# mic4606_power_v2.net
KiCad netlist of a schematic drawn in EAGLE
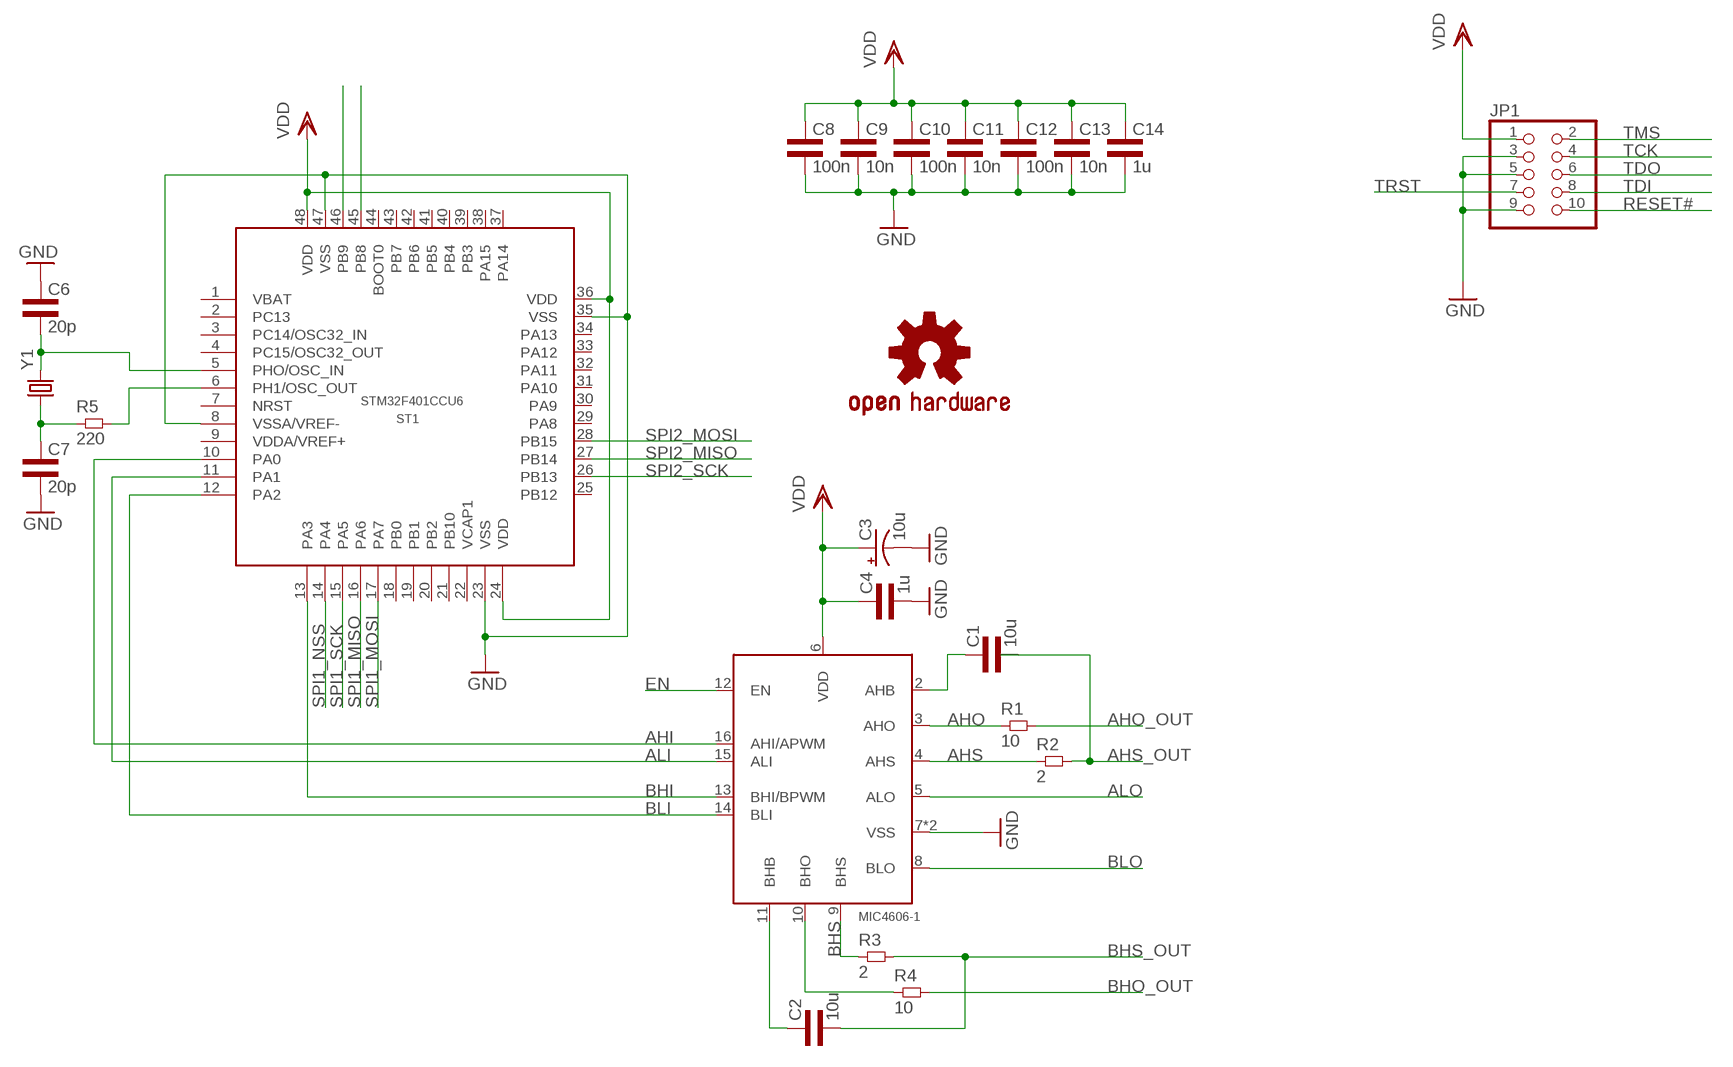
[diagram p0: schematic, sheet 1]
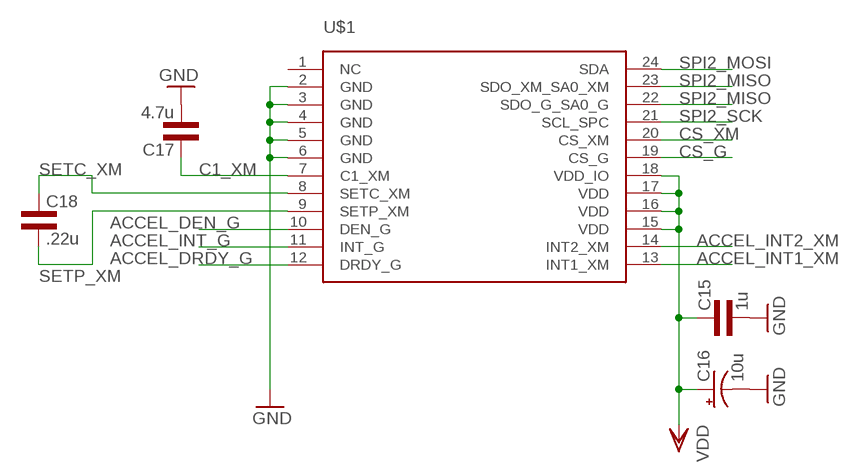
[diagram p1: schematic, sheet 2]
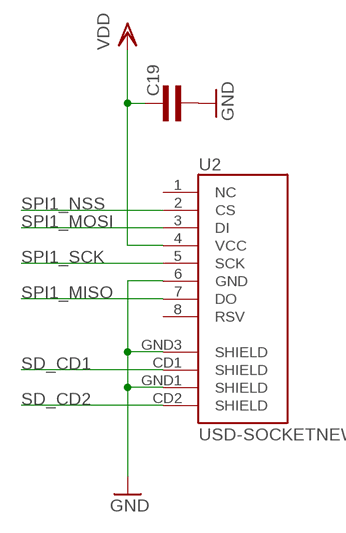
[diagram p2: schematic, sheet 3]
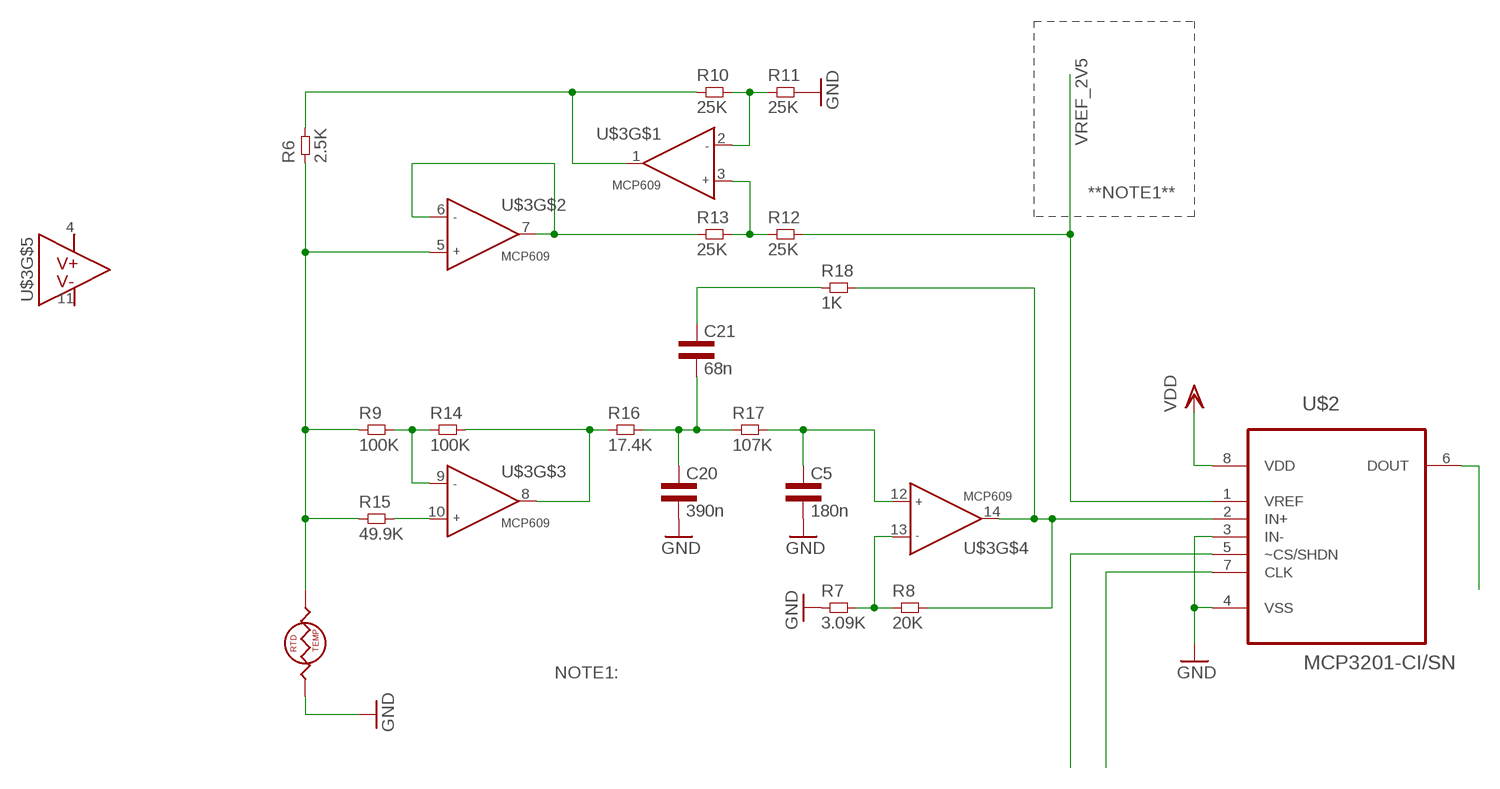
[diagram p3: schematic, sheet 4]

(export (version "E")
  (design (tool "Eeschema 10.0.6"))
  (components
    (comp (ref "C1")
      (value "10u")
      (footprint "eagle-import:0805L3")
      (libsource (lib "eagle-import") (part "CAP0805L3"))
    )
    (comp (ref "C2")
      (value "10u")
      (footprint "eagle-import:0805L3")
      (libsource (lib "eagle-import") (part "CAP0805L3"))
    )
    (comp (ref "C3")
      (value "10u")
      (footprint "eagle-import:E1,8-4")
      (libsource (lib "eagle-import") (part "CPOL-USE1.8-4"))
    )
    (comp (ref "C4")
      (value "1u")
      (footprint "eagle-import:0603L3")
      (libsource (lib "eagle-import") (part "CAP0603L3"))
    )
    (comp (ref "C6")
      (value "20p")
      (footprint "eagle-import:0603L3")
      (libsource (lib "eagle-import") (part "CAP0603L3"))
    )
    (comp (ref "C7")
      (value "20p")
      (footprint "eagle-import:0603L3")
      (libsource (lib "eagle-import") (part "CAP0603L3"))
    )
    (comp (ref "C8")
      (value "100n")
      (footprint "eagle-import:0603L3")
      (libsource (lib "eagle-import") (part "CAP0603L3"))
    )
    (comp (ref "C9")
      (value "10n")
      (footprint "eagle-import:0603L3")
      (libsource (lib "eagle-import") (part "CAP0603L3"))
    )
    (comp (ref "C10")
      (value "100n")
      (footprint "eagle-import:0603L3")
      (libsource (lib "eagle-import") (part "CAP0603L3"))
    )
    (comp (ref "C11")
      (value "10n")
      (footprint "eagle-import:0603L3")
      (libsource (lib "eagle-import") (part "CAP0603L3"))
    )
    (comp (ref "C12")
      (value "100n")
      (footprint "eagle-import:0603L3")
      (libsource (lib "eagle-import") (part "CAP0603L3"))
    )
    (comp (ref "C13")
      (value "10n")
      (footprint "eagle-import:0603L3")
      (libsource (lib "eagle-import") (part "CAP0603L3"))
    )
    (comp (ref "C14")
      (value "1u")
      (footprint "eagle-import:0805L3")
      (libsource (lib "eagle-import") (part "CAP0805L3"))
    )
    (comp (ref "JP1")
      (value "PINHD-2X5")
      (footprint "eagle-import:2X05")
      (libsource (lib "eagle-import") (part "PINHD-2X5"))
    )
    (comp (ref "LOGO1")
      (value "OSHW-LOGOM")
      (footprint "eagle-import:OSHW-LOGO-M")
      (libsource (lib "eagle-import") (part "OSHW-LOGOM"))
    )
    (comp (ref "MD1")
      (value "MIC4606-1")
      (footprint "eagle-import:QFN44-16LD-PL-2")
      (libsource (lib "eagle-import") (part "MIC4606-1"))
    )
    (comp (ref "R1")
      (value "10")
      (footprint "eagle-import:0805L3")
      (libsource (lib "eagle-import") (part "RES0805L3"))
    )
    (comp (ref "R2")
      (value "2")
      (footprint "eagle-import:0805L3")
      (libsource (lib "eagle-import") (part "RES0805L3"))
    )
    (comp (ref "R3")
      (value "2")
      (footprint "eagle-import:0805L3")
      (libsource (lib "eagle-import") (part "RES0805L3"))
    )
    (comp (ref "R4")
      (value "10")
      (footprint "eagle-import:0805L3")
      (libsource (lib "eagle-import") (part "RES0805L3"))
    )
    (comp (ref "R5")
      (value "220")
      (footprint "eagle-import:0603L3")
      (libsource (lib "eagle-import") (part "RES0603L3"))
    )
    (comp (ref "ST1")
      (value "STM32F401CCU6")
      (footprint "eagle-import:UFQFPN48")
      (libsource (lib "eagle-import") (part "STM32F401CCU6"))
    )
    (comp (ref "Y1")
      (value "CRYSTALHC49US")
      (footprint "eagle-import:HC49US")
      (libsource (lib "eagle-import") (part "CRYSTALHC49US"))
    )
    (comp (ref "C19")
      (value "CAP0603L3")
      (footprint "eagle-import:0603L3")
      (libsource (lib "eagle-import") (part "CAP0603L3"))
    )
    (comp (ref "U2")
      (value "USD-SOCKETNEW")
      (footprint "eagle-import:MICRO-SD-SOCKET-PP")
      (libsource (lib "eagle-import") (part "USD-SOCKETNEW"))
    )
    (comp (ref "C15")
      (value "1u")
      (footprint "eagle-import:0805L3")
      (libsource (lib "eagle-import") (part "CAP0805L3"))
    )
    (comp (ref "C16")
      (value "10u")
      (footprint "eagle-import:CT3216")
      (libsource (lib "eagle-import") (part "CPOL-USCT3216"))
    )
    (comp (ref "C17")
      (value "4.7u")
      (footprint "eagle-import:0603L3")
      (libsource (lib "eagle-import") (part "CAP0603L3"))
    )
    (comp (ref "C18")
      (value ".22u")
      (footprint "eagle-import:0603L3")
      (libsource (lib "eagle-import") (part "CAP0603L3"))
    )
    (comp (ref "U$1")
      (value "ST_LSM9DS0_TEMP_SENSE_LSM9DS0")
      (footprint "eagle-import:ST_LSM9DS0_TEMP_SENSE_LGA-24")
      (libsource (lib "eagle-import") (part "ST_LSM9DS0_TEMP_SENSE_LSM9DS0"))
    )
    (comp (ref "C5")
      (value "180n")
      (footprint "eagle-import:0603L3")
      (libsource (lib "eagle-import") (part "CAP0603L3"))
    )
    (comp (ref "C20")
      (value "390n")
      (footprint "eagle-import:0603L3")
      (libsource (lib "eagle-import") (part "CAP0603L3"))
    )
    (comp (ref "C21")
      (value "68n")
      (footprint "eagle-import:0603L3")
      (libsource (lib "eagle-import") (part "CAP0603L3"))
    )
    (comp (ref "R6")
      (value "2.5K")
      (footprint "eagle-import:0603L3")
      (libsource (lib "eagle-import") (part "RES0603L3"))
    )
    (comp (ref "R7")
      (value "3.09K")
      (footprint "eagle-import:0603L3")
      (libsource (lib "eagle-import") (part "RES0603L3"))
    )
    (comp (ref "R8")
      (value "20K")
      (footprint "eagle-import:0603L3")
      (libsource (lib "eagle-import") (part "RES0603L3"))
    )
    (comp (ref "R9")
      (value "100K")
      (footprint "eagle-import:0603L3")
      (libsource (lib "eagle-import") (part "RES0603L3"))
    )
    (comp (ref "R10")
      (value "25K")
      (footprint "eagle-import:0603L3")
      (libsource (lib "eagle-import") (part "RES0603L3"))
    )
    (comp (ref "R11")
      (value "25K")
      (footprint "eagle-import:0603L3")
      (libsource (lib "eagle-import") (part "RES0603L3"))
    )
    (comp (ref "R12")
      (value "25K")
      (footprint "eagle-import:0603L3")
      (libsource (lib "eagle-import") (part "RES0603L3"))
    )
    (comp (ref "R13")
      (value "25K")
      (footprint "eagle-import:0603L3")
      (libsource (lib "eagle-import") (part "RES0603L3"))
    )
    (comp (ref "R14")
      (value "100K")
      (footprint "eagle-import:0603L3")
      (libsource (lib "eagle-import") (part "RES0603L3"))
    )
    (comp (ref "R15")
      (value "49.9K")
      (footprint "eagle-import:0603L3")
      (libsource (lib "eagle-import") (part "RES0603L3"))
    )
    (comp (ref "R16")
      (value "17.4K")
      (footprint "eagle-import:0603L3")
      (libsource (lib "eagle-import") (part "RES0603L3"))
    )
    (comp (ref "R17")
      (value "107K")
      (footprint "eagle-import:0603L3")
      (libsource (lib "eagle-import") (part "RES0603L3"))
    )
    (comp (ref "R18")
      (value "1K")
      (footprint "eagle-import:0603L3")
      (libsource (lib "eagle-import") (part "RES0603L3"))
    )
    (comp (ref "RTD1")
      (value "RTD0805L1")
      (footprint "eagle-import:0805L1")
      (libsource (lib "eagle-import") (part "RTD0805L1"))
    )
    (comp (ref "U$2")
      (value "MCP3201-CI/SN")
      (footprint "eagle-import:SOIC127P600X175-8N")
      (libsource (lib "eagle-import") (part "MCP3201-CI/SN"))
    )
    (comp (ref "U$3")
      (value "MCP609")
      (footprint "eagle-import:TSSOP-14")
      (libsource (lib "eagle-import") (part "MCP609"))
    )
  )
  (nets
    (net (code "1") (name "ACCEL_DEN_G") (class "Default")
      (node (ref "U$1") (pin "10") (pinfunction "DEN_G_10") (pintype "bidirectional"))
    )
    (net (code "2") (name "ACCEL_DRDY_G") (class "Default")
      (node (ref "U$1") (pin "12") (pinfunction "DRDY_G_12") (pintype "bidirectional"))
    )
    (net (code "3") (name "ACCEL_INT1_XM") (class "Default")
      (node (ref "U$1") (pin "13") (pinfunction "INT1_XM_13") (pintype "bidirectional"))
    )
    (net (code "4") (name "ACCEL_INT2_XM") (class "Default")
      (node (ref "U$1") (pin "14") (pinfunction "INT2_XM_14") (pintype "bidirectional"))
    )
    (net (code "5") (name "ACCEL_INT_G") (class "Default")
      (node (ref "U$1") (pin "11") (pinfunction "INT_G_11") (pintype "bidirectional"))
    )
    (net (code "6") (name "AHI") (class "Default")
      (node (ref "MD1") (pin "16") (pinfunction "AHI/APWM_16") (pintype "bidirectional"))
      (node (ref "ST1") (pin "10") (pinfunction "PA0_10") (pintype "bidirectional"))
    )
    (net (code "7") (name "AHO") (class "Default")
      (node (ref "MD1") (pin "3") (pinfunction "AHO_3") (pintype "bidirectional"))
      (node (ref "R1") (pin "1") (pinfunction "1_1") (pintype "bidirectional"))
    )
    (net (code "8") (name "AHO_OUT") (class "Default")
      (node (ref "R1") (pin "2") (pinfunction "2_2") (pintype "bidirectional"))
    )
    (net (code "9") (name "AHS") (class "Default")
      (node (ref "MD1") (pin "4") (pinfunction "AHS_4") (pintype "bidirectional"))
      (node (ref "R2") (pin "1") (pinfunction "1_1") (pintype "bidirectional"))
    )
    (net (code "10") (name "AHS_OUT") (class "Default")
      (node (ref "C1") (pin "2") (pinfunction "2_2") (pintype "bidirectional"))
      (node (ref "R2") (pin "2") (pinfunction "2_2") (pintype "bidirectional"))
    )
    (net (code "11") (name "ALI") (class "Default")
      (node (ref "MD1") (pin "15") (pinfunction "ALI_15") (pintype "bidirectional"))
      (node (ref "ST1") (pin "11") (pinfunction "PA1_11") (pintype "bidirectional"))
    )
    (net (code "12") (name "ALO") (class "Default")
      (node (ref "MD1") (pin "5") (pinfunction "ALO_5") (pintype "bidirectional"))
    )
    (net (code "13") (name "BHI") (class "Default")
      (node (ref "MD1") (pin "13") (pinfunction "BHI/BPWM_13") (pintype "bidirectional"))
      (node (ref "ST1") (pin "13") (pinfunction "PA3_13") (pintype "bidirectional"))
    )
    (net (code "14") (name "BHO_OUT") (class "Default")
      (node (ref "R4") (pin "2") (pinfunction "2_2") (pintype "bidirectional"))
    )
    (net (code "15") (name "BHS") (class "Default")
      (node (ref "MD1") (pin "9") (pinfunction "BHS_9") (pintype "bidirectional"))
      (node (ref "R3") (pin "1") (pinfunction "1_1") (pintype "bidirectional"))
    )
    (net (code "16") (name "BHS_OUT") (class "Default")
      (node (ref "C2") (pin "2") (pinfunction "2_2") (pintype "bidirectional"))
      (node (ref "R3") (pin "2") (pinfunction "2_2") (pintype "bidirectional"))
    )
    (net (code "17") (name "BLI") (class "Default")
      (node (ref "MD1") (pin "14") (pinfunction "BLI_14") (pintype "bidirectional"))
      (node (ref "ST1") (pin "12") (pinfunction "PA2_12") (pintype "bidirectional"))
    )
    (net (code "18") (name "BLO") (class "Default")
      (node (ref "MD1") (pin "8") (pinfunction "BLO_8") (pintype "bidirectional"))
    )
    (net (code "19") (name "C1_XM") (class "Default")
      (node (ref "C17") (pin "P$1") (pinfunction "1_P$1") (pintype "bidirectional"))
      (node (ref "U$1") (pin "7") (pinfunction "C1_XM_7") (pintype "bidirectional"))
    )
    (net (code "20") (name "CS_G") (class "Default")
      (node (ref "ST1") (pin "45") (pinfunction "PB8_45") (pintype "bidirectional"))
      (node (ref "U$1") (pin "19") (pinfunction "CS_G_19") (pintype "bidirectional"))
    )
    (net (code "21") (name "CS_XM") (class "Default")
      (node (ref "ST1") (pin "46") (pinfunction "PB9_46") (pintype "bidirectional"))
      (node (ref "U$1") (pin "20") (pinfunction "CS_XM_20") (pintype "bidirectional"))
    )
    (net (code "22") (name "EN") (class "Default")
      (node (ref "MD1") (pin "12") (pinfunction "EN_12") (pintype "bidirectional"))
    )
    (net (code "23") (name "GND") (class "Default")
      (node (ref "C10") (pin "P$2") (pinfunction "2_P$2") (pintype "bidirectional"))
      (node (ref "C11") (pin "P$2") (pinfunction "2_P$2") (pintype "bidirectional"))
      (node (ref "C12") (pin "P$2") (pinfunction "2_P$2") (pintype "bidirectional"))
      (node (ref "C13") (pin "P$2") (pinfunction "2_P$2") (pintype "bidirectional"))
      (node (ref "C14") (pin "2") (pinfunction "2_2") (pintype "bidirectional"))
      (node (ref "C15") (pin "2") (pinfunction "2_2") (pintype "bidirectional"))
      (node (ref "C16") (pin "-") (pinfunction "-_-") (pintype "passive"))
      (node (ref "C17") (pin "P$2") (pinfunction "2_P$2") (pintype "bidirectional"))
      (node (ref "C19") (pin "P$2") (pinfunction "2_P$2") (pintype "bidirectional"))
      (node (ref "C20") (pin "P$2") (pinfunction "2_P$2") (pintype "bidirectional"))
      (node (ref "C3") (pin "-") (pinfunction "-_-") (pintype "passive"))
      (node (ref "C4") (pin "P$2") (pinfunction "2_P$2") (pintype "bidirectional"))
      (node (ref "C5") (pin "P$2") (pinfunction "2_P$2") (pintype "bidirectional"))
      (node (ref "C6") (pin "P$1") (pinfunction "1_P$1") (pintype "bidirectional"))
      (node (ref "C7") (pin "P$2") (pinfunction "2_P$2") (pintype "bidirectional"))
      (node (ref "C8") (pin "P$2") (pinfunction "2_P$2") (pintype "bidirectional"))
      (node (ref "C9") (pin "P$2") (pinfunction "2_P$2") (pintype "bidirectional"))
      (node (ref "JP1") (pin "3") (pinfunction "3_3") (pintype "passive"))
      (node (ref "JP1") (pin "5") (pinfunction "5_5") (pintype "passive"))
      (node (ref "JP1") (pin "9") (pinfunction "9_9") (pintype "passive"))
      (node (ref "MD1") (pin "7") (pinfunction "VSS_7") (pintype "bidirectional"))
      (node (ref "MD1") (pin "TP") (pinfunction "VSS_TP") (pintype "bidirectional"))
      (node (ref "R11") (pin "P$2") (pinfunction "2_P$2") (pintype "bidirectional"))
      (node (ref "R7") (pin "P$1") (pinfunction "1_P$1") (pintype "bidirectional"))
      (node (ref "RTD1") (pin "1") (pinfunction "1_1") (pintype "bidirectional"))
      (node (ref "ST1") (pin "23") (pinfunction "VSS_23") (pintype "bidirectional"))
      (node (ref "ST1") (pin "35") (pinfunction "VSS_35") (pintype "bidirectional"))
      (node (ref "ST1") (pin "47") (pinfunction "VSS_47") (pintype "bidirectional"))
      (node (ref "ST1") (pin "8") (pinfunction "VSSA/VREF-_8") (pintype "bidirectional"))
      (node (ref "U$1") (pin "2") (pinfunction "GND_2") (pintype "bidirectional"))
      (node (ref "U$1") (pin "3") (pinfunction "GND_3") (pintype "bidirectional"))
      (node (ref "U$1") (pin "4") (pinfunction "GND_4") (pintype "bidirectional"))
      (node (ref "U$1") (pin "5") (pinfunction "GND_5") (pintype "bidirectional"))
      (node (ref "U$1") (pin "6") (pinfunction "GND_6") (pintype "bidirectional"))
      (node (ref "U$2") (pin "3") (pinfunction "IN-_3") (pintype "input"))
      (node (ref "U$2") (pin "4") (pinfunction "VSS_4") (pintype "power_in"))
      (node (ref "U2") (pin "6") (pinfunction "GND_6") (pintype "bidirectional"))
      (node (ref "U2") (pin "GND1") (pinfunction "SHIELD_GND1") (pintype "bidirectional"))
      (node (ref "U2") (pin "GND3") (pinfunction "SHIELD_GND3") (pintype "bidirectional"))
    )
    (net (code "24") (name "Net-(C5-1)") (class "Default")
      (node (ref "C5") (pin "P$1") (pinfunction "1_P$1") (pintype "bidirectional"))
      (node (ref "R17") (pin "P$2") (pinfunction "2_P$2") (pintype "bidirectional"))
      (node (ref "U$3") (pin "12") (pinfunction "INA+_12") (pintype "bidirectional"))
    )
    (net (code "25") (name "Net-(C6-2)") (class "Default")
      (node (ref "C6") (pin "P$2") (pinfunction "2_P$2") (pintype "bidirectional"))
      (node (ref "ST1") (pin "5") (pinfunction "PHO/OSC_IN_5") (pintype "bidirectional"))
      (node (ref "Y1") (pin "2") (pinfunction "2_2") (pintype "passive"))
    )
    (net (code "26") (name "Net-(C7-1)") (class "Default")
      (node (ref "C7") (pin "P$1") (pinfunction "1_P$1") (pintype "bidirectional"))
      (node (ref "R5") (pin "P$1") (pinfunction "1_P$1") (pintype "bidirectional"))
      (node (ref "Y1") (pin "1") (pinfunction "1_1") (pintype "passive"))
    )
    (net (code "27") (name "Net-(C20-1)") (class "Default")
      (node (ref "C20") (pin "P$1") (pinfunction "1_P$1") (pintype "bidirectional"))
      (node (ref "C21") (pin "P$2") (pinfunction "2_P$2") (pintype "bidirectional"))
      (node (ref "R16") (pin "P$2") (pinfunction "2_P$2") (pintype "bidirectional"))
      (node (ref "R17") (pin "P$1") (pinfunction "1_P$1") (pintype "bidirectional"))
    )
    (net (code "28") (name "Net-(C21-1)") (class "Default")
      (node (ref "C21") (pin "P$1") (pinfunction "1_P$1") (pintype "bidirectional"))
      (node (ref "R18") (pin "P$1") (pinfunction "1_P$1") (pintype "bidirectional"))
    )
    (net (code "29") (name "Net-(MD1-AHB)") (class "Default")
      (node (ref "C1") (pin "1") (pinfunction "1_1") (pintype "bidirectional"))
      (node (ref "MD1") (pin "2") (pinfunction "AHB_2") (pintype "bidirectional"))
    )
    (net (code "30") (name "Net-(MD1-BHB)") (class "Default")
      (node (ref "C2") (pin "1") (pinfunction "1_1") (pintype "bidirectional"))
      (node (ref "MD1") (pin "11") (pinfunction "BHB_11") (pintype "bidirectional"))
    )
    (net (code "31") (name "Net-(MD1-BHO)") (class "Default")
      (node (ref "MD1") (pin "10") (pinfunction "BHO_10") (pintype "bidirectional"))
      (node (ref "R4") (pin "1") (pinfunction "1_1") (pintype "bidirectional"))
    )
    (net (code "32") (name "Net-(R5-2)") (class "Default")
      (node (ref "R5") (pin "P$2") (pinfunction "2_P$2") (pintype "bidirectional"))
      (node (ref "ST1") (pin "6") (pinfunction "PH1/OSC_OUT_6") (pintype "bidirectional"))
    )
    (net (code "33") (name "Net-(R7-2)") (class "Default")
      (node (ref "R7") (pin "P$2") (pinfunction "2_P$2") (pintype "bidirectional"))
      (node (ref "R8") (pin "P$1") (pinfunction "1_P$1") (pintype "bidirectional"))
      (node (ref "U$3") (pin "13") (pinfunction "INA-_13") (pintype "bidirectional"))
    )
    (net (code "34") (name "Net-(R10-1)") (class "Default")
      (node (ref "R10") (pin "P$1") (pinfunction "1_P$1") (pintype "bidirectional"))
      (node (ref "R6") (pin "P$2") (pinfunction "2_P$2") (pintype "bidirectional"))
      (node (ref "U$3") (pin "1") (pinfunction "OUTA_1") (pintype "bidirectional"))
    )
    (net (code "35") (name "Net-(R10-2)") (class "Default")
      (node (ref "R10") (pin "P$2") (pinfunction "2_P$2") (pintype "bidirectional"))
      (node (ref "R11") (pin "P$1") (pinfunction "1_P$1") (pintype "bidirectional"))
      (node (ref "U$3") (pin "2") (pinfunction "INA-_2") (pintype "bidirectional"))
    )
    (net (code "36") (name "Net-(R12-1)") (class "Default")
      (node (ref "R12") (pin "P$1") (pinfunction "1_P$1") (pintype "bidirectional"))
      (node (ref "R13") (pin "P$2") (pinfunction "2_P$2") (pintype "bidirectional"))
      (node (ref "U$3") (pin "3") (pinfunction "INA+_3") (pintype "bidirectional"))
    )
    (net (code "37") (name "Net-(R13-1)") (class "Default")
      (node (ref "R13") (pin "P$1") (pinfunction "1_P$1") (pintype "bidirectional"))
      (node (ref "U$3") (pin "6") (pinfunction "INA-_6") (pintype "bidirectional"))
      (node (ref "U$3") (pin "7") (pinfunction "OUTA_7") (pintype "bidirectional"))
    )
    (net (code "38") (name "Net-(R14-1)") (class "Default")
      (node (ref "R14") (pin "P$1") (pinfunction "1_P$1") (pintype "bidirectional"))
      (node (ref "R9") (pin "P$2") (pinfunction "2_P$2") (pintype "bidirectional"))
      (node (ref "U$3") (pin "9") (pinfunction "INA-_9") (pintype "bidirectional"))
    )
    (net (code "39") (name "Net-(R14-2)") (class "Default")
      (node (ref "R14") (pin "P$2") (pinfunction "2_P$2") (pintype "bidirectional"))
      (node (ref "R16") (pin "P$1") (pinfunction "1_P$1") (pintype "bidirectional"))
      (node (ref "U$3") (pin "8") (pinfunction "OUTA_8") (pintype "bidirectional"))
    )
    (net (code "40") (name "Net-(R15-1)") (class "Default")
      (node (ref "R15") (pin "P$1") (pinfunction "1_P$1") (pintype "bidirectional"))
      (node (ref "R6") (pin "P$1") (pinfunction "1_P$1") (pintype "bidirectional"))
      (node (ref "R9") (pin "P$1") (pinfunction "1_P$1") (pintype "bidirectional"))
      (node (ref "RTD1") (pin "2") (pinfunction "2_2") (pintype "bidirectional"))
      (node (ref "U$3") (pin "5") (pinfunction "INA+_5") (pintype "bidirectional"))
    )
    (net (code "41") (name "Net-(R15-2)") (class "Default")
      (node (ref "R15") (pin "P$2") (pinfunction "2_P$2") (pintype "bidirectional"))
      (node (ref "U$3") (pin "10") (pinfunction "INA+_10") (pintype "bidirectional"))
    )
    (net (code "42") (name "Net-(R18-2)") (class "Default")
      (node (ref "R18") (pin "P$2") (pinfunction "2_P$2") (pintype "bidirectional"))
      (node (ref "R8") (pin "P$2") (pinfunction "2_P$2") (pintype "bidirectional"))
      (node (ref "U$2") (pin "2") (pinfunction "IN+_2") (pintype "input"))
      (node (ref "U$3") (pin "14") (pinfunction "OUTA_14") (pintype "bidirectional"))
    )
    (net (code "43") (name "RESET#") (class "Default")
      (node (ref "JP1") (pin "10") (pinfunction "10_10") (pintype "passive"))
    )
    (net (code "44") (name "SD_CD1") (class "Default")
      (node (ref "U2") (pin "CD1") (pinfunction "SHIELD_CD1") (pintype "bidirectional"))
    )
    (net (code "45") (name "SD_CD2") (class "Default")
      (node (ref "U2") (pin "CD2") (pinfunction "SHIELD_CD2") (pintype "bidirectional"))
    )
    (net (code "46") (name "SETC_XM") (class "Default")
      (node (ref "C18") (pin "P$1") (pinfunction "1_P$1") (pintype "bidirectional"))
      (node (ref "U$1") (pin "8") (pinfunction "SETC_XM_8") (pintype "bidirectional"))
    )
    (net (code "47") (name "SETP_XM") (class "Default")
      (node (ref "C18") (pin "P$2") (pinfunction "2_P$2") (pintype "bidirectional"))
      (node (ref "U$1") (pin "9") (pinfunction "SETP_XM_9") (pintype "bidirectional"))
    )
    (net (code "48") (name "SPI1_MISO") (class "Default")
      (node (ref "ST1") (pin "16") (pinfunction "PA6_16") (pintype "bidirectional"))
      (node (ref "U2") (pin "7") (pinfunction "DO_7") (pintype "bidirectional"))
    )
    (net (code "49") (name "SPI1_MOSI") (class "Default")
      (node (ref "ST1") (pin "17") (pinfunction "PA7_17") (pintype "bidirectional"))
      (node (ref "U2") (pin "3") (pinfunction "DI_3") (pintype "bidirectional"))
    )
    (net (code "50") (name "SPI1_NSS") (class "Default")
      (node (ref "ST1") (pin "14") (pinfunction "PA4_14") (pintype "bidirectional"))
      (node (ref "U2") (pin "2") (pinfunction "CS_2") (pintype "bidirectional"))
    )
    (net (code "51") (name "SPI1_SCK") (class "Default")
      (node (ref "ST1") (pin "15") (pinfunction "PA5_15") (pintype "bidirectional"))
      (node (ref "U2") (pin "5") (pinfunction "SCK_5") (pintype "bidirectional"))
    )
    (net (code "52") (name "SPI2_MISO") (class "Default")
      (node (ref "ST1") (pin "27") (pinfunction "PB14_27") (pintype "bidirectional"))
      (node (ref "U$1") (pin "22") (pinfunction "SDO_G_SA0_G_22") (pintype "bidirectional"))
      (node (ref "U$1") (pin "23") (pinfunction "SDO_XM_SA0_XM_23") (pintype "bidirectional"))
    )
    (net (code "53") (name "SPI2_MOSI") (class "Default")
      (node (ref "ST1") (pin "28") (pinfunction "PB15_28") (pintype "bidirectional"))
      (node (ref "U$1") (pin "24") (pinfunction "SDA_24") (pintype "bidirectional"))
    )
    (net (code "54") (name "SPI2_SCK") (class "Default")
      (node (ref "ST1") (pin "26") (pinfunction "PB13_26") (pintype "bidirectional"))
      (node (ref "U$1") (pin "21") (pinfunction "SCL_SPC_21") (pintype "bidirectional"))
    )
    (net (code "55") (name "TCK") (class "Default")
      (node (ref "JP1") (pin "4") (pinfunction "4_4") (pintype "passive"))
    )
    (net (code "56") (name "TDI") (class "Default")
      (node (ref "JP1") (pin "8") (pinfunction "8_8") (pintype "passive"))
    )
    (net (code "57") (name "TDO") (class "Default")
      (node (ref "JP1") (pin "6") (pinfunction "6_6") (pintype "passive"))
    )
    (net (code "58") (name "TMS") (class "Default")
      (node (ref "JP1") (pin "2") (pinfunction "2_2") (pintype "passive"))
    )
    (net (code "59") (name "TRST") (class "Default")
      (node (ref "JP1") (pin "7") (pinfunction "7_7") (pintype "passive"))
    )
    (net (code "60") (name "V+") (class "Default")
      (node (ref "U$3") (pin "4") (pinfunction "V+_4") (pintype "power_in"))
    )
    (net (code "61") (name "V-") (class "Default")
      (node (ref "U$3") (pin "11") (pinfunction "V-_11") (pintype "power_in"))
    )
    (net (code "62") (name "VDD") (class "Default")
      (node (ref "C10") (pin "P$1") (pinfunction "1_P$1") (pintype "bidirectional"))
      (node (ref "C11") (pin "P$1") (pinfunction "1_P$1") (pintype "bidirectional"))
      (node (ref "C12") (pin "P$1") (pinfunction "1_P$1") (pintype "bidirectional"))
      (node (ref "C13") (pin "P$1") (pinfunction "1_P$1") (pintype "bidirectional"))
      (node (ref "C14") (pin "1") (pinfunction "1_1") (pintype "bidirectional"))
      (node (ref "C15") (pin "1") (pinfunction "1_1") (pintype "bidirectional"))
      (node (ref "C16") (pin "+") (pinfunction "+_+") (pintype "passive"))
      (node (ref "C19") (pin "P$1") (pinfunction "1_P$1") (pintype "bidirectional"))
      (node (ref "C3") (pin "+") (pinfunction "+_+") (pintype "passive"))
      (node (ref "C4") (pin "P$1") (pinfunction "1_P$1") (pintype "bidirectional"))
      (node (ref "C8") (pin "P$1") (pinfunction "1_P$1") (pintype "bidirectional"))
      (node (ref "C9") (pin "P$1") (pinfunction "1_P$1") (pintype "bidirectional"))
      (node (ref "JP1") (pin "1") (pinfunction "1_1") (pintype "passive"))
      (node (ref "MD1") (pin "6") (pinfunction "VDD_6") (pintype "bidirectional"))
      (node (ref "ST1") (pin "24") (pinfunction "VDD_24") (pintype "bidirectional"))
      (node (ref "ST1") (pin "36") (pinfunction "VDD_36") (pintype "bidirectional"))
      (node (ref "ST1") (pin "48") (pinfunction "VDD_48") (pintype "bidirectional"))
      (node (ref "U$1") (pin "15") (pinfunction "VDD_15") (pintype "bidirectional"))
      (node (ref "U$1") (pin "16") (pinfunction "VDD_16") (pintype "bidirectional"))
      (node (ref "U$1") (pin "17") (pinfunction "VDD_17") (pintype "bidirectional"))
      (node (ref "U$1") (pin "18") (pinfunction "VDD_IO_18") (pintype "bidirectional"))
      (node (ref "U$2") (pin "8") (pinfunction "VDD_8") (pintype "power_in"))
      (node (ref "U2") (pin "4") (pinfunction "VCC_4") (pintype "bidirectional"))
    )
    (net (code "63") (name "VREF_2V5") (class "Default")
      (node (ref "R12") (pin "P$2") (pinfunction "2_P$2") (pintype "bidirectional"))
      (node (ref "U$2") (pin "1") (pinfunction "VREF_1") (pintype "input"))
    )
    (net (code "64") (name "unconnected-(ST1-BOOT0-Pad44)") (class "Default")
      (node (ref "ST1") (pin "44") (pinfunction "BOOT0_44") (pintype "bidirectional"))
    )
    (net (code "65") (name "unconnected-(ST1-NRST-Pad7)") (class "Default")
      (node (ref "ST1") (pin "7") (pinfunction "NRST_7") (pintype "bidirectional"))
    )
    (net (code "66") (name "unconnected-(ST1-PA8-Pad29)") (class "Default")
      (node (ref "ST1") (pin "29") (pinfunction "PA8_29") (pintype "bidirectional"))
    )
    (net (code "67") (name "unconnected-(ST1-PA9-Pad30)") (class "Default")
      (node (ref "ST1") (pin "30") (pinfunction "PA9_30") (pintype "bidirectional"))
    )
    (net (code "68") (name "unconnected-(ST1-PA10-Pad31)") (class "Default")
      (node (ref "ST1") (pin "31") (pinfunction "PA10_31") (pintype "bidirectional"))
    )
    (net (code "69") (name "unconnected-(ST1-PA11-Pad32)") (class "Default")
      (node (ref "ST1") (pin "32") (pinfunction "PA11_32") (pintype "bidirectional"))
    )
    (net (code "70") (name "unconnected-(ST1-PA12-Pad33)") (class "Default")
      (node (ref "ST1") (pin "33") (pinfunction "PA12_33") (pintype "bidirectional"))
    )
    (net (code "71") (name "unconnected-(ST1-PA13-Pad34)") (class "Default")
      (node (ref "ST1") (pin "34") (pinfunction "PA13_34") (pintype "bidirectional"))
    )
    (net (code "72") (name "unconnected-(ST1-PA14-Pad37)") (class "Default")
      (node (ref "ST1") (pin "37") (pinfunction "PA14_37") (pintype "bidirectional"))
    )
    (net (code "73") (name "unconnected-(ST1-PA15-Pad38)") (class "Default")
      (node (ref "ST1") (pin "38") (pinfunction "PA15_38") (pintype "bidirectional"))
    )
    (net (code "74") (name "unconnected-(ST1-PB0-Pad18)") (class "Default")
      (node (ref "ST1") (pin "18") (pinfunction "PB0_18") (pintype "bidirectional"))
    )
    (net (code "75") (name "unconnected-(ST1-PB1-Pad19)") (class "Default")
      (node (ref "ST1") (pin "19") (pinfunction "PB1_19") (pintype "bidirectional"))
    )
    (net (code "76") (name "unconnected-(ST1-PB2-Pad20)") (class "Default")
      (node (ref "ST1") (pin "20") (pinfunction "PB2_20") (pintype "bidirectional"))
    )
    (net (code "77") (name "unconnected-(ST1-PB3-Pad39)") (class "Default")
      (node (ref "ST1") (pin "39") (pinfunction "PB3_39") (pintype "bidirectional"))
    )
    (net (code "78") (name "unconnected-(ST1-PB4-Pad40)") (class "Default")
      (node (ref "ST1") (pin "40") (pinfunction "PB4_40") (pintype "bidirectional"))
    )
    (net (code "79") (name "unconnected-(ST1-PB5-Pad41)") (class "Default")
      (node (ref "ST1") (pin "41") (pinfunction "PB5_41") (pintype "bidirectional"))
    )
    (net (code "80") (name "unconnected-(ST1-PB6-Pad42)") (class "Default")
      (node (ref "ST1") (pin "42") (pinfunction "PB6_42") (pintype "bidirectional"))
    )
    (net (code "81") (name "unconnected-(ST1-PB7-Pad43)") (class "Default")
      (node (ref "ST1") (pin "43") (pinfunction "PB7_43") (pintype "bidirectional"))
    )
    (net (code "82") (name "unconnected-(ST1-PB10-Pad21)") (class "Default")
      (node (ref "ST1") (pin "21") (pinfunction "PB10_21") (pintype "bidirectional"))
    )
    (net (code "83") (name "unconnected-(ST1-PB12-Pad25)") (class "Default")
      (node (ref "ST1") (pin "25") (pinfunction "PB12_25") (pintype "bidirectional"))
    )
    (net (code "84") (name "unconnected-(ST1-PC13-Pad2)") (class "Default")
      (node (ref "ST1") (pin "2") (pinfunction "PC13_2") (pintype "bidirectional"))
    )
    (net (code "85") (name "unconnected-(ST1-PC14{slash}OSC32_IN-Pad3)") (class "Default")
      (node (ref "ST1") (pin "3") (pinfunction "PC14/OSC32_IN_3") (pintype "bidirectional"))
    )
    (net (code "86") (name "unconnected-(ST1-PC15{slash}OSC32_OUT-Pad4)") (class "Default")
      (node (ref "ST1") (pin "4") (pinfunction "PC15/OSC32_OUT_4") (pintype "bidirectional"))
    )
    (net (code "87") (name "unconnected-(ST1-VBAT-Pad1)") (class "Default")
      (node (ref "ST1") (pin "1") (pinfunction "VBAT_1") (pintype "bidirectional"))
    )
    (net (code "88") (name "unconnected-(ST1-VCAP1-Pad22)") (class "Default")
      (node (ref "ST1") (pin "22") (pinfunction "VCAP1_22") (pintype "bidirectional"))
    )
    (net (code "89") (name "unconnected-(ST1-VDDA{slash}VREF+-Pad9)") (class "Default")
      (node (ref "ST1") (pin "9") (pinfunction "VDDA/VREF+_9") (pintype "bidirectional"))
    )
    (net (code "90") (name "unconnected-(U$1-NC-Pad1)") (class "Default")
      (node (ref "U$1") (pin "1") (pinfunction "NC_1") (pintype "bidirectional"))
    )
    (net (code "91") (name "unconnected-(U$2-CLK-Pad7)") (class "Default")
      (node (ref "U$2") (pin "7") (pinfunction "CLK_7") (pintype "input"))
    )
    (net (code "92") (name "unconnected-(U$2-DOUT-Pad6)") (class "Default")
      (node (ref "U$2") (pin "6") (pinfunction "DOUT_6") (pintype "output"))
    )
    (net (code "93") (name "unconnected-(U$2-~{CS{slash}SHDN}-Pad5)") (class "Default")
      (node (ref "U$2") (pin "5") (pinfunction "~{CS/SHDN}_5") (pintype "input"))
    )
    (net (code "94") (name "unconnected-(U2-NC-Pad1)") (class "Default")
      (node (ref "U2") (pin "1") (pinfunction "NC_1") (pintype "bidirectional"))
    )
    (net (code "95") (name "unconnected-(U2-RSV-Pad8)") (class "Default")
      (node (ref "U2") (pin "8") (pinfunction "RSV_8") (pintype "bidirectional"))
    )
  )
)
